# WifiAC-controller.net
KiCad netlist of a schematic drawn in EAGLE
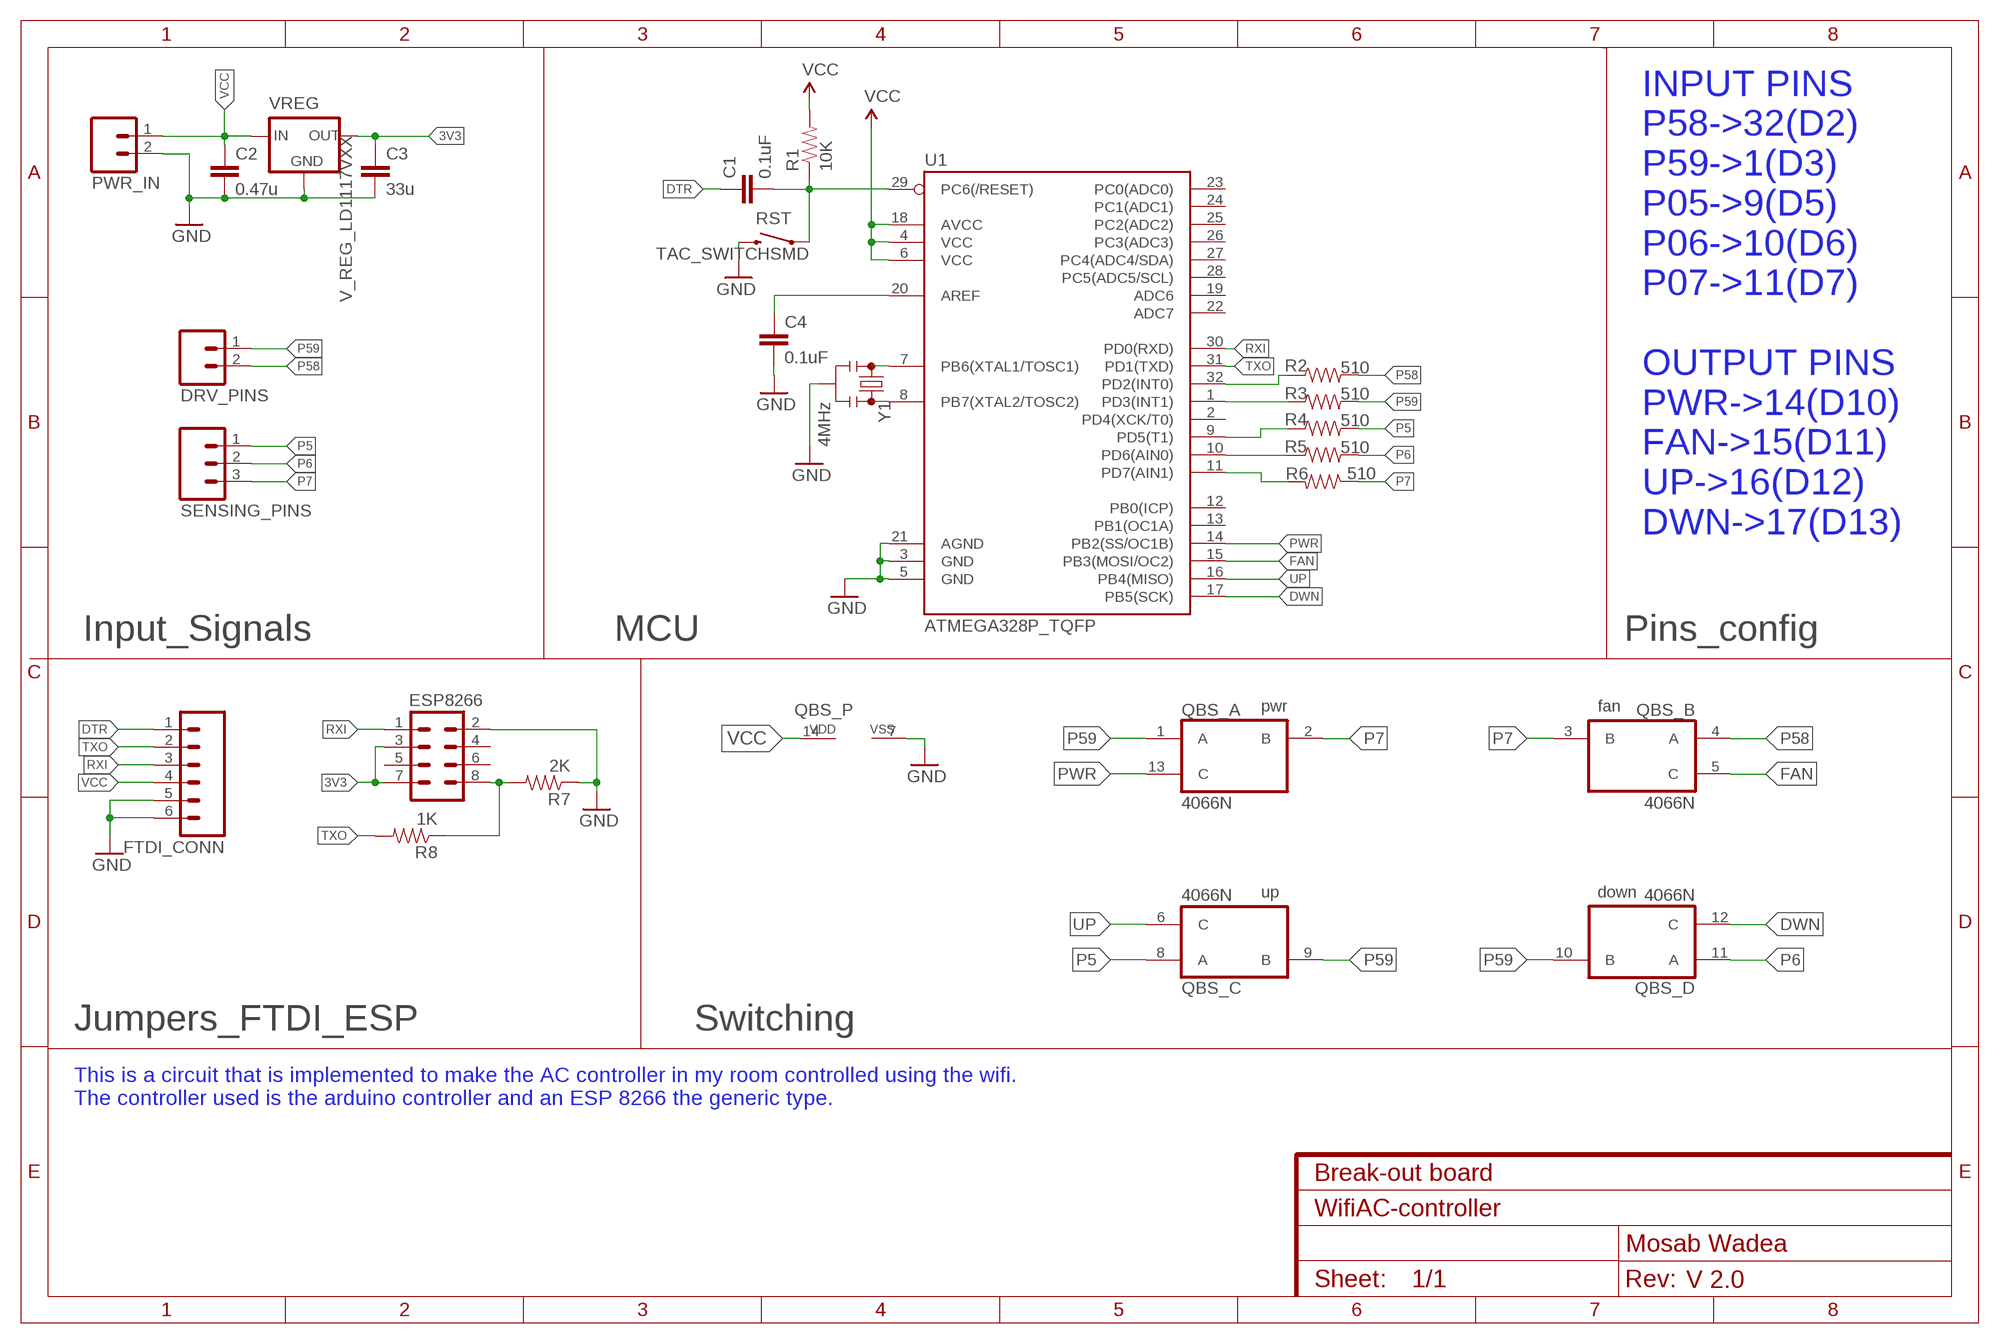
[diagram p0: schematic, sheet 1]

(export (version "E")
  (design (tool "Eeschema 10.0.6"))
  (components
    (comp (ref "C1")
      (value "0.1uF")
      (footprint "eagle-import:0805")
      (libsource (lib "eagle-import") (part "CAP0805"))
    )
    (comp (ref "C2")
      (value "0.47u")
      (footprint "eagle-import:0805")
      (libsource (lib "eagle-import") (part "CAP0805"))
    )
    (comp (ref "C3")
      (value "33u")
      (footprint "eagle-import:0805")
      (libsource (lib "eagle-import") (part "CAP0805"))
    )
    (comp (ref "C4")
      (value "0.1uF")
      (footprint "eagle-import:0805")
      (libsource (lib "eagle-import") (part "CAP0805"))
    )
    (comp (ref "DRV_PINS")
      (value "M02POLAR")
      (footprint "eagle-import:MOLEX-1X2")
      (libsource (lib "eagle-import") (part "M02POLAR"))
    )
    (comp (ref "ESP8266")
      (value "M04X2")
      (footprint "eagle-import:2X4")
      (libsource (lib "eagle-import") (part "M04X2"))
    )
    (comp (ref "FTDI_CONN")
      (value "M06NO_SILK_FEMALE_PTH")
      (footprint "eagle-import:1X06_NO_SILK")
      (libsource (lib "eagle-import") (part "M06NO_SILK_FEMALE_PTH"))
    )
    (comp (ref "PWR_IN")
      (value "M02POLAR")
      (footprint "eagle-import:MOLEX-1X2")
      (libsource (lib "eagle-import") (part "M02POLAR"))
    )
    (comp (ref "QBS_")
      (value "4066N")
      (footprint "eagle-import:DIL14")
      (libsource (lib "eagle-import") (part "4066N"))
    )
    (comp (ref "R1")
      (value "10K")
      (footprint "eagle-import:0805")
      (libsource (lib "eagle-import") (part "RESISTOR0805-RES"))
    )
    (comp (ref "R2")
      (value "510")
      (footprint "eagle-import:0805")
      (libsource (lib "eagle-import") (part "RESISTOR0805-RES"))
    )
    (comp (ref "R3")
      (value "510")
      (footprint "eagle-import:0805")
      (libsource (lib "eagle-import") (part "RESISTOR0805-RES"))
    )
    (comp (ref "R4")
      (value "510")
      (footprint "eagle-import:0805")
      (libsource (lib "eagle-import") (part "RESISTOR0805-RES"))
    )
    (comp (ref "R5")
      (value "510")
      (footprint "eagle-import:0805")
      (libsource (lib "eagle-import") (part "RESISTOR0805-RES"))
    )
    (comp (ref "R6")
      (value "510")
      (footprint "eagle-import:0805")
      (libsource (lib "eagle-import") (part "RESISTOR0805-RES"))
    )
    (comp (ref "R7")
      (value "2K")
      (footprint "eagle-import:0805")
      (libsource (lib "eagle-import") (part "RESISTOR0805-RES"))
    )
    (comp (ref "R8")
      (value "1K")
      (footprint "eagle-import:0805")
      (libsource (lib "eagle-import") (part "RESISTOR0805-RES"))
    )
    (comp (ref "RST")
      (value "TAC_SWITCHSMD")
      (footprint "eagle-import:TACTILE-SWITCH-SMD")
      (libsource (lib "eagle-import") (part "SWITCH-MOMENTARY-2SMD-REDUNDANT"))
    )
    (comp (ref "SENSING_PINS")
      (value "M03POLAR")
      (footprint "eagle-import:MOLEX-1X3")
      (libsource (lib "eagle-import") (part "M03POLAR"))
    )
    (comp (ref "U1")
      (value "ATMEGA328P_TQFP")
      (footprint "eagle-import:TQFP32-08")
      (libsource (lib "eagle-import") (part "ATMEGA328P_TQFP"))
    )
    (comp (ref "VREG")
      (value "V_REG_LD1117VXX")
      (footprint "eagle-import:78XXL")
      (libsource (lib "eagle-import") (part "V_REG_LD1117VXX"))
    )
    (comp (ref "Y1")
      (value "4MHz")
      (footprint "eagle-import:RESONATOR-SMD_MED")
      (libsource (lib "eagle-import") (part "RESONATOR4MHZ"))
    )
  )
  (nets
    (net (code "1") (name "3V3") (class "Default")
      (node (ref "C3") (pin "1") (pinfunction "1_1") (pintype "passive"))
      (node (ref "ESP8266") (pin "3") (pinfunction "3_3") (pintype "passive"))
      (node (ref "ESP8266") (pin "7") (pinfunction "7_7") (pintype "passive"))
      (node (ref "VREG") (pin "GND") (pinfunction "OUT_GND") (pintype "passive"))
    )
    (net (code "2") (name "DTR") (class "Default")
      (node (ref "C1") (pin "1") (pinfunction "1_1") (pintype "passive"))
      (node (ref "FTDI_CONN") (pin "1") (pinfunction "1_1") (pintype "passive"))
    )
    (net (code "3") (name "DWN") (class "Default")
      (node (ref "QBS_") (pin "12") (pinfunction "C_12") (pintype "input"))
      (node (ref "U1") (pin "17") (pinfunction "PB5(SCK)_17") (pintype "bidirectional"))
    )
    (net (code "4") (name "FAN") (class "Default")
      (node (ref "QBS_") (pin "5") (pinfunction "C_5") (pintype "input"))
      (node (ref "U1") (pin "15") (pinfunction "PB3(MOSI/OC2)_15") (pintype "bidirectional"))
    )
    (net (code "5") (name "GND") (class "Default")
      (node (ref "C2") (pin "2") (pinfunction "2_2") (pintype "passive"))
      (node (ref "C3") (pin "2") (pinfunction "2_2") (pintype "passive"))
      (node (ref "C4") (pin "2") (pinfunction "2_2") (pintype "passive"))
      (node (ref "ESP8266") (pin "2") (pinfunction "2_2") (pintype "passive"))
      (node (ref "FTDI_CONN") (pin "5") (pinfunction "5_5") (pintype "passive"))
      (node (ref "FTDI_CONN") (pin "6") (pinfunction "6_6") (pintype "passive"))
      (node (ref "PWR_IN") (pin "2") (pinfunction "2_2") (pintype "passive"))
      (node (ref "QBS_") (pin "7") (pinfunction "VSS_7") (pintype "power_in"))
      (node (ref "R7") (pin "1") (pinfunction "1_1") (pintype "passive"))
      (node (ref "RST") (pin "3") (pinfunction "2_3") (pintype "passive"))
      (node (ref "RST") (pin "4") (pinfunction "2_4") (pintype "passive"))
      (node (ref "U1") (pin "21") (pinfunction "AGND_21") (pintype "bidirectional"))
      (node (ref "U1") (pin "3") (pinfunction "GND_3") (pintype "bidirectional"))
      (node (ref "U1") (pin "5") (pinfunction "GND_5") (pintype "bidirectional"))
      (node (ref "VREG") (pin "IN") (pinfunction "GND_IN") (pintype "input"))
      (node (ref "Y1") (pin "2") (pinfunction "2_2") (pintype "passive"))
    )
    (net (code "6") (name "Net-(ESP8266-Pad8)") (class "Default")
      (node (ref "ESP8266") (pin "8") (pinfunction "8_8") (pintype "passive"))
      (node (ref "R7") (pin "2") (pinfunction "2_2") (pintype "passive"))
      (node (ref "R8") (pin "1") (pinfunction "1_1") (pintype "passive"))
    )
    (net (code "7") (name "Net-(U1-AREF)") (class "Default")
      (node (ref "C4") (pin "1") (pinfunction "1_1") (pintype "passive"))
      (node (ref "U1") (pin "20") (pinfunction "AREF_20") (pintype "bidirectional"))
    )
    (net (code "8") (name "Net-(U1-PB6(XTAL1{slash}TOSC1))") (class "Default")
      (node (ref "U1") (pin "7") (pinfunction "PB6(XTAL1/TOSC1)_7") (pintype "bidirectional"))
      (node (ref "Y1") (pin "1") (pinfunction "1_1") (pintype "passive"))
    )
    (net (code "9") (name "Net-(U1-PB7(XTAL2{slash}TOSC2))") (class "Default")
      (node (ref "U1") (pin "8") (pinfunction "PB7(XTAL2/TOSC2)_8") (pintype "bidirectional"))
      (node (ref "Y1") (pin "3") (pinfunction "3_3") (pintype "passive"))
    )
    (net (code "10") (name "Net-(U1-PC6({slash}RESET))") (class "Default")
      (node (ref "C1") (pin "2") (pinfunction "2_2") (pintype "passive"))
      (node (ref "R1") (pin "1") (pinfunction "1_1") (pintype "passive"))
      (node (ref "RST") (pin "1") (pinfunction "1_1") (pintype "passive"))
      (node (ref "RST") (pin "2") (pinfunction "1_2") (pintype "passive"))
      (node (ref "U1") (pin "29") (pinfunction "PC6(/RESET)_29") (pintype "bidirectional"))
    )
    (net (code "11") (name "Net-(U1-PD2(INT0))") (class "Default")
      (node (ref "R2") (pin "1") (pinfunction "1_1") (pintype "passive"))
      (node (ref "U1") (pin "32") (pinfunction "PD2(INT0)_32") (pintype "bidirectional"))
    )
    (net (code "12") (name "Net-(U1-PD3(INT1))") (class "Default")
      (node (ref "R3") (pin "1") (pinfunction "1_1") (pintype "passive"))
      (node (ref "U1") (pin "1") (pinfunction "PD3(INT1)_1") (pintype "bidirectional"))
    )
    (net (code "13") (name "Net-(U1-PD5(T1))") (class "Default")
      (node (ref "R4") (pin "1") (pinfunction "1_1") (pintype "passive"))
      (node (ref "U1") (pin "9") (pinfunction "PD5(T1)_9") (pintype "bidirectional"))
    )
    (net (code "14") (name "Net-(U1-PD6(AIN0))") (class "Default")
      (node (ref "R5") (pin "1") (pinfunction "1_1") (pintype "passive"))
      (node (ref "U1") (pin "10") (pinfunction "PD6(AIN0)_10") (pintype "bidirectional"))
    )
    (net (code "15") (name "Net-(U1-PD7(AIN1))") (class "Default")
      (node (ref "R6") (pin "2") (pinfunction "2_2") (pintype "passive"))
      (node (ref "U1") (pin "11") (pinfunction "PD7(AIN1)_11") (pintype "bidirectional"))
    )
    (net (code "16") (name "P5") (class "Default")
      (node (ref "QBS_") (pin "8") (pinfunction "A_8") (pintype "tri_state"))
      (node (ref "R4") (pin "2") (pinfunction "2_2") (pintype "passive"))
      (node (ref "SENSING_PINS") (pin "1") (pinfunction "1_1") (pintype "passive"))
    )
    (net (code "17") (name "P6") (class "Default")
      (node (ref "QBS_") (pin "11") (pinfunction "A_11") (pintype "tri_state"))
      (node (ref "R5") (pin "2") (pinfunction "2_2") (pintype "passive"))
      (node (ref "SENSING_PINS") (pin "2") (pinfunction "2_2") (pintype "passive"))
    )
    (net (code "18") (name "P7") (class "Default")
      (node (ref "QBS_") (pin "2") (pinfunction "B_2") (pintype "tri_state"))
      (node (ref "QBS_") (pin "3") (pinfunction "B_3") (pintype "tri_state"))
      (node (ref "R6") (pin "1") (pinfunction "1_1") (pintype "passive"))
      (node (ref "SENSING_PINS") (pin "3") (pinfunction "3_3") (pintype "passive"))
    )
    (net (code "19") (name "P58") (class "Default")
      (node (ref "DRV_PINS") (pin "2") (pinfunction "2_2") (pintype "passive"))
      (node (ref "QBS_") (pin "4") (pinfunction "A_4") (pintype "tri_state"))
      (node (ref "R2") (pin "2") (pinfunction "2_2") (pintype "passive"))
    )
    (net (code "20") (name "P59") (class "Default")
      (node (ref "DRV_PINS") (pin "1") (pinfunction "1_1") (pintype "passive"))
      (node (ref "QBS_") (pin "1") (pinfunction "A_1") (pintype "tri_state"))
      (node (ref "QBS_") (pin "10") (pinfunction "B_10") (pintype "tri_state"))
      (node (ref "QBS_") (pin "9") (pinfunction "B_9") (pintype "tri_state"))
      (node (ref "R3") (pin "2") (pinfunction "2_2") (pintype "passive"))
    )
    (net (code "21") (name "PWR") (class "Default")
      (node (ref "QBS_") (pin "13") (pinfunction "C_13") (pintype "input"))
      (node (ref "U1") (pin "14") (pinfunction "PB2(SS/OC1B)_14") (pintype "bidirectional"))
    )
    (net (code "22") (name "RXI") (class "Default")
      (node (ref "ESP8266") (pin "1") (pinfunction "1_1") (pintype "passive"))
      (node (ref "FTDI_CONN") (pin "3") (pinfunction "3_3") (pintype "passive"))
      (node (ref "U1") (pin "30") (pinfunction "PD0(RXD)_30") (pintype "bidirectional"))
    )
    (net (code "23") (name "TXO") (class "Default")
      (node (ref "FTDI_CONN") (pin "2") (pinfunction "2_2") (pintype "passive"))
      (node (ref "R8") (pin "2") (pinfunction "2_2") (pintype "passive"))
      (node (ref "U1") (pin "31") (pinfunction "PD1(TXD)_31") (pintype "bidirectional"))
    )
    (net (code "24") (name "UP") (class "Default")
      (node (ref "QBS_") (pin "6") (pinfunction "C_6") (pintype "input"))
      (node (ref "U1") (pin "16") (pinfunction "PB4(MISO)_16") (pintype "bidirectional"))
    )
    (net (code "25") (name "VCC") (class "Default")
      (node (ref "C2") (pin "1") (pinfunction "1_1") (pintype "passive"))
      (node (ref "FTDI_CONN") (pin "4") (pinfunction "4_4") (pintype "passive"))
      (node (ref "PWR_IN") (pin "1") (pinfunction "1_1") (pintype "passive"))
      (node (ref "QBS_") (pin "14") (pinfunction "VDD_14") (pintype "power_in"))
      (node (ref "R1") (pin "2") (pinfunction "2_2") (pintype "passive"))
      (node (ref "U1") (pin "18") (pinfunction "AVCC_18") (pintype "bidirectional"))
      (node (ref "U1") (pin "4") (pinfunction "VCC_4") (pintype "bidirectional"))
      (node (ref "U1") (pin "6") (pinfunction "VCC_6") (pintype "bidirectional"))
      (node (ref "VREG") (pin "OUT") (pinfunction "IN_OUT") (pintype "input"))
    )
    (net (code "26") (name "unconnected-(ESP8266-Pad4)") (class "Default")
      (node (ref "ESP8266") (pin "4") (pinfunction "4_4") (pintype "passive"))
    )
    (net (code "27") (name "unconnected-(ESP8266-Pad5)") (class "Default")
      (node (ref "ESP8266") (pin "5") (pinfunction "5_5") (pintype "passive"))
    )
    (net (code "28") (name "unconnected-(ESP8266-Pad6)") (class "Default")
      (node (ref "ESP8266") (pin "6") (pinfunction "6_6") (pintype "passive"))
    )
    (net (code "29") (name "unconnected-(U1-ADC6-Pad19)") (class "Default")
      (node (ref "U1") (pin "19") (pinfunction "ADC6_19") (pintype "bidirectional"))
    )
    (net (code "30") (name "unconnected-(U1-ADC7-Pad22)") (class "Default")
      (node (ref "U1") (pin "22") (pinfunction "ADC7_22") (pintype "bidirectional"))
    )
    (net (code "31") (name "unconnected-(U1-PB0(ICP)-Pad12)") (class "Default")
      (node (ref "U1") (pin "12") (pinfunction "PB0(ICP)_12") (pintype "bidirectional"))
    )
    (net (code "32") (name "unconnected-(U1-PB1(OC1A)-Pad13)") (class "Default")
      (node (ref "U1") (pin "13") (pinfunction "PB1(OC1A)_13") (pintype "bidirectional"))
    )
    (net (code "33") (name "unconnected-(U1-PC0(ADC0)-Pad23)") (class "Default")
      (node (ref "U1") (pin "23") (pinfunction "PC0(ADC0)_23") (pintype "bidirectional"))
    )
    (net (code "34") (name "unconnected-(U1-PC1(ADC1)-Pad24)") (class "Default")
      (node (ref "U1") (pin "24") (pinfunction "PC1(ADC1)_24") (pintype "bidirectional"))
    )
    (net (code "35") (name "unconnected-(U1-PC2(ADC2)-Pad25)") (class "Default")
      (node (ref "U1") (pin "25") (pinfunction "PC2(ADC2)_25") (pintype "bidirectional"))
    )
    (net (code "36") (name "unconnected-(U1-PC3(ADC3)-Pad26)") (class "Default")
      (node (ref "U1") (pin "26") (pinfunction "PC3(ADC3)_26") (pintype "bidirectional"))
    )
    (net (code "37") (name "unconnected-(U1-PC4(ADC4{slash}SDA)-Pad27)") (class "Default")
      (node (ref "U1") (pin "27") (pinfunction "PC4(ADC4/SDA)_27") (pintype "bidirectional"))
    )
    (net (code "38") (name "unconnected-(U1-PC5(ADC5{slash}SCL)-Pad28)") (class "Default")
      (node (ref "U1") (pin "28") (pinfunction "PC5(ADC5/SCL)_28") (pintype "bidirectional"))
    )
    (net (code "39") (name "unconnected-(U1-PD4(XCK{slash}T0)-Pad2)") (class "Default")
      (node (ref "U1") (pin "2") (pinfunction "PD4(XCK/T0)_2") (pintype "bidirectional"))
    )
  )
)
